# FPGA3.net
KiCad netlist of a schematic drawn in Altium Designer
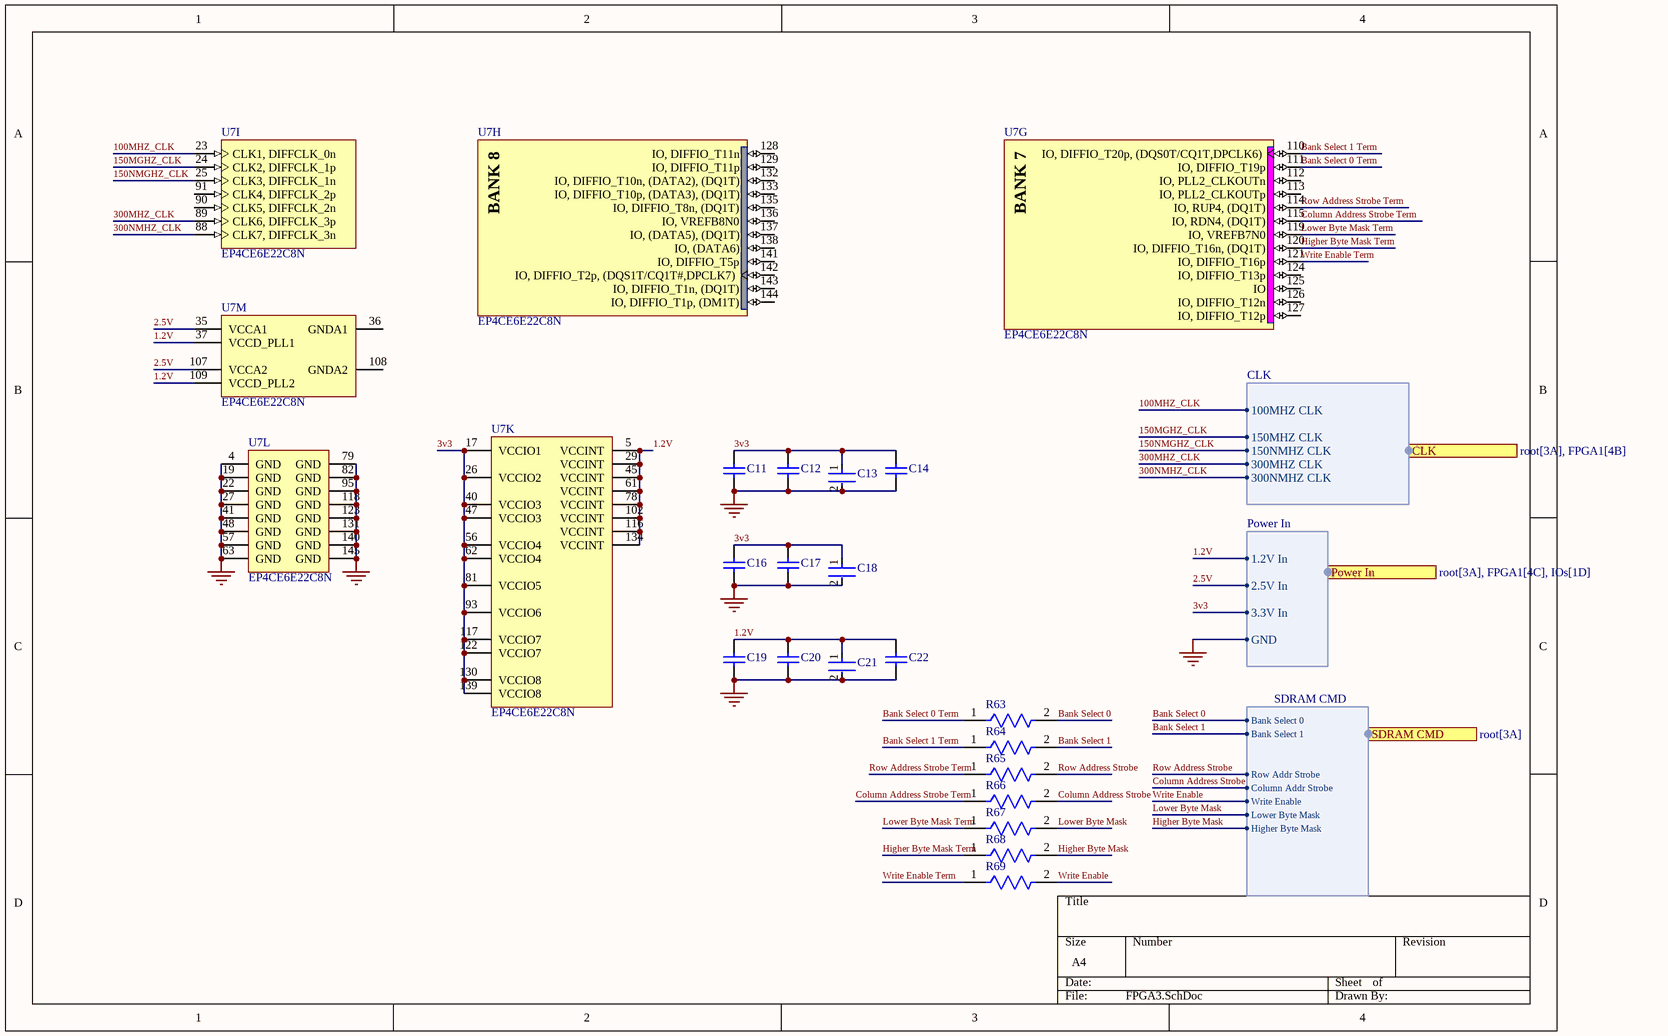
[diagram p0: FPGA3.SchDoc]

(export (version "E")
  (design (tool "Eeschema 10.0.6"))
  (components
    (comp (ref "C11")
      (value "C0603C105K9PACTU")
      (footprint "CAPC1608X90X35LL15T15")
      (fields (field (name "MANUFACTURER") "Kemet"))
      (libsource (lib "Altium Content Vault") (part "CAP"))
    )
    (comp (ref "C12")
      (value "C0603C105K9PACTU")
      (footprint "CAPC1608X90X35LL15T15")
      (fields (field (name "MANUFACTURER") "Kemet"))
      (libsource (lib "Altium Content Vault") (part "CAP"))
    )
    (comp (ref "C13")
      (value "GCG188R91H104MA01D")
      (footprint "FP-GCG188-0_2-IPC_B")
      (libsource (lib "Altium Content Vault") (part "02cd4be3c70576c341d710602a673aa"))
    )
    (comp (ref "C14")
      (value "C0805S472K5RACTU")
      (footprint "CAPC2013X145X50ML20T25")
      (fields (field (name "MANUFACTURER") "Kemet"))
      (libsource (lib "Altium Content Vault") (part "CAP"))
    )
    (comp (ref "C16")
      (value "C0603S102K4RACTU")
      (footprint "CAPC1608X87X35ML15T15")
      (fields (field (name "MANUFACTURER") "Kemet"))
      (libsource (lib "Altium Content Vault") (part "CAP"))
    )
    (comp (ref "C17")
      (value "C0805S472K5RACTU")
      (footprint "CAPC2013X145X50ML20T25")
      (fields (field (name "MANUFACTURER") "Kemet"))
      (libsource (lib "Altium Content Vault") (part "CAP"))
    )
    (comp (ref "C18")
      (value "GCG188R91H104MA01D")
      (footprint "FP-GCG188-0_2-IPC_B")
      (libsource (lib "Altium Content Vault") (part "02cd4be3c70576c341d710602a673aa"))
    )
    (comp (ref "C19")
      (value "C0603C105K9PACTU")
      (footprint "CAPC1608X90X35LL15T15")
      (fields (field (name "MANUFACTURER") "Kemet"))
      (libsource (lib "Altium Content Vault") (part "CAP"))
    )
    (comp (ref "C20")
      (value "C0603C105K9PACTU")
      (footprint "CAPC1608X90X35LL15T15")
      (fields (field (name "MANUFACTURER") "Kemet"))
      (libsource (lib "Altium Content Vault") (part "CAP"))
    )
    (comp (ref "C21")
      (value "GCG188R91H104MA01D")
      (footprint "FP-GCG188-0_2-IPC_B")
      (libsource (lib "Altium Content Vault") (part "02cd4be3c70576c341d710602a673aa"))
    )
    (comp (ref "C22")
      (value "C0805S472K5RACTU")
      (footprint "CAPC2013X145X50ML20T25")
      (fields (field (name "MANUFACTURER") "Kemet"))
      (libsource (lib "Altium Content Vault") (part "CAP"))
    )
    (comp (ref "R63")
      (value "RT0402BRE0750RL")
      (footprint "FP-RT0402-0_35-MFG")
      (fields (field (name "TOLERANCE") "0.1%"))
      (libsource (lib "Altium Content Vault") (part "1029c3af85768c4190bb7ad29bc67b5"))
    )
    (comp (ref "R64")
      (value "RT0402BRE0750RL")
      (footprint "FP-RT0402-0_35-MFG")
      (fields (field (name "TOLERANCE") "0.1%"))
      (libsource (lib "Altium Content Vault") (part "1029c3af85768c4190bb7ad29bc67b5"))
    )
    (comp (ref "R65")
      (value "RT0402BRE0750RL")
      (footprint "FP-RT0402-0_35-MFG")
      (fields (field (name "TOLERANCE") "0.1%"))
      (libsource (lib "Altium Content Vault") (part "1029c3af85768c4190bb7ad29bc67b5"))
    )
    (comp (ref "R66")
      (value "RT0402BRE0750RL")
      (footprint "FP-RT0402-0_35-MFG")
      (fields (field (name "TOLERANCE") "0.1%"))
      (libsource (lib "Altium Content Vault") (part "1029c3af85768c4190bb7ad29bc67b5"))
    )
    (comp (ref "R67")
      (value "RT0402BRE0750RL")
      (footprint "FP-RT0402-0_35-MFG")
      (fields (field (name "TOLERANCE") "0.1%"))
      (libsource (lib "Altium Content Vault") (part "1029c3af85768c4190bb7ad29bc67b5"))
    )
    (comp (ref "R68")
      (value "RT0402BRE0750RL")
      (footprint "FP-RT0402-0_35-MFG")
      (fields (field (name "TOLERANCE") "0.1%"))
      (libsource (lib "Altium Content Vault") (part "1029c3af85768c4190bb7ad29bc67b5"))
    )
    (comp (ref "R69")
      (value "RT0402BRE0750RL")
      (footprint "FP-RT0402-0_35-MFG")
      (fields (field (name "TOLERANCE") "0.1%"))
      (libsource (lib "Altium Content Vault") (part "1029c3af85768c4190bb7ad29bc67b5"))
    )
    (comp (ref "U7")
      (value "EP4CE6E22C8N")
      (footprint "EQFP144_A-165_D2-54_M")
      (fields (field (name "MANUFACTURER") "Altera"))
      (libsource (lib "Altium Content Vault") (part "FPGA-ALEP4C-EP4CE6-E144"))
    )
  )
  (nets
    (net (code "6") (name "/1.2V") (class "Default")
      (node (ref "C19") (pin "2") (pinfunction "2_2") (pintype "passive"))
      (node (ref "C20") (pin "2") (pinfunction "2_2") (pintype "passive"))
      (node (ref "C21") (pin "1") (pinfunction "1_1") (pintype "passive"))
      (node (ref "C22") (pin "2") (pinfunction "2_2") (pintype "passive"))
      (node (ref "U7") (pin "102") (pinfunction "VCCINT_102") (pintype "power_in"))
      (node (ref "U7") (pin "109") (pinfunction "VCCD_PLL2_109") (pintype "power_in"))
      (node (ref "U7") (pin "116") (pinfunction "VCCINT_116") (pintype "power_in"))
      (node (ref "U7") (pin "134") (pinfunction "VCCINT_134") (pintype "power_in"))
      (node (ref "U7") (pin "29") (pinfunction "VCCINT_29") (pintype "power_in"))
      (node (ref "U7") (pin "37") (pinfunction "VCCD_PLL1_37") (pintype "power_in"))
      (node (ref "U7") (pin "45") (pinfunction "VCCINT_45") (pintype "power_in"))
      (node (ref "U7") (pin "5") (pinfunction "VCCINT_5") (pintype "power_in"))
      (node (ref "U7") (pin "61") (pinfunction "VCCINT_61") (pintype "power_in"))
      (node (ref "U7") (pin "78") (pinfunction "VCCINT_78") (pintype "power_in"))
    )
    (net (code "7") (name "/2.5V") (class "Default")
      (node (ref "U7") (pin "107") (pinfunction "VCCA2_107") (pintype "power_in"))
      (node (ref "U7") (pin "35") (pinfunction "VCCA1_35") (pintype "power_in"))
    )
    (net (code "8") (name "/3v3") (class "Default")
      (node (ref "C11") (pin "2") (pinfunction "2_2") (pintype "passive"))
      (node (ref "C12") (pin "2") (pinfunction "2_2") (pintype "passive"))
      (node (ref "C13") (pin "1") (pinfunction "1_1") (pintype "passive"))
      (node (ref "C14") (pin "2") (pinfunction "2_2") (pintype "passive"))
      (node (ref "C16") (pin "2") (pinfunction "2_2") (pintype "passive"))
      (node (ref "C17") (pin "2") (pinfunction "2_2") (pintype "passive"))
      (node (ref "C18") (pin "1") (pinfunction "1_1") (pintype "passive"))
      (node (ref "U7") (pin "117") (pinfunction "VCCIO7_117") (pintype "power_in"))
      (node (ref "U7") (pin "122") (pinfunction "VCCIO7_122") (pintype "power_in"))
      (node (ref "U7") (pin "130") (pinfunction "VCCIO8_130") (pintype "power_in"))
      (node (ref "U7") (pin "139") (pinfunction "VCCIO8_139") (pintype "power_in"))
      (node (ref "U7") (pin "17") (pinfunction "VCCIO1_17") (pintype "power_in"))
      (node (ref "U7") (pin "26") (pinfunction "VCCIO2_26") (pintype "power_in"))
      (node (ref "U7") (pin "40") (pinfunction "VCCIO3_40") (pintype "power_in"))
      (node (ref "U7") (pin "47") (pinfunction "VCCIO3_47") (pintype "power_in"))
      (node (ref "U7") (pin "56") (pinfunction "VCCIO4_56") (pintype "power_in"))
      (node (ref "U7") (pin "62") (pinfunction "VCCIO4_62") (pintype "power_in"))
      (node (ref "U7") (pin "81") (pinfunction "VCCIO5_81") (pintype "power_in"))
      (node (ref "U7") (pin "93") (pinfunction "VCCIO6_93") (pintype "power_in"))
    )
    (net (code "9") (name "/100MHZ_CLK") (class "Default")
      (node (ref "U7") (pin "23") (pinfunction "CLK1,_DIFFCLK_0n_23") (pintype "input"))
    )
    (net (code "10") (name "/150MGHZ_CLK") (class "Default")
      (node (ref "U7") (pin "24") (pinfunction "CLK2,_DIFFCLK_1p_24") (pintype "input"))
    )
    (net (code "11") (name "/150NMGHZ_CLK") (class "Default")
      (node (ref "U7") (pin "25") (pinfunction "CLK3,_DIFFCLK_1n_25") (pintype "input"))
    )
    (net (code "12") (name "/300MHZ_CLK") (class "Default")
      (node (ref "U7") (pin "89") (pinfunction "CLK6,_DIFFCLK_3p_89") (pintype "input"))
    )
    (net (code "13") (name "/300NMHZ_CLK") (class "Default")
      (node (ref "U7") (pin "88") (pinfunction "CLK7,_DIFFCLK_3n_88") (pintype "input"))
    )
    (net (code "14") (name "/Bank Select 0") (class "Default")
      (node (ref "R63") (pin "2") (pinfunction "2_2") (pintype "passive"))
    )
    (net (code "15") (name "/Bank Select 0 Term") (class "Default")
      (node (ref "R63") (pin "1") (pinfunction "1_1") (pintype "passive"))
      (node (ref "U7") (pin "111") (pinfunction "IO,_DIFFIO_T19p_111") (pintype "bidirectional"))
    )
    (net (code "16") (name "/Bank Select 1") (class "Default")
      (node (ref "R64") (pin "2") (pinfunction "2_2") (pintype "passive"))
    )
    (net (code "17") (name "/Bank Select 1 Term") (class "Default")
      (node (ref "R64") (pin "1") (pinfunction "1_1") (pintype "passive"))
      (node (ref "U7") (pin "110") (pinfunction "IO,_DIFFIO_T20p,_(DQS0T/CQ1T,DPCLK6)_110") (pintype "bidirectional"))
    )
    (net (code "18") (name "/Column Address Strobe") (class "Default")
      (node (ref "R66") (pin "2") (pinfunction "2_2") (pintype "passive"))
    )
    (net (code "19") (name "/Column Address Strobe Term") (class "Default")
      (node (ref "R66") (pin "1") (pinfunction "1_1") (pintype "passive"))
      (node (ref "U7") (pin "115") (pinfunction "IO,_RDN4,_(DQ1T)_115") (pintype "bidirectional"))
    )
    (net (code "20") (name "/Higher Byte Mask") (class "Default")
      (node (ref "R68") (pin "2") (pinfunction "2_2") (pintype "passive"))
    )
    (net (code "21") (name "/Higher Byte Mask Term") (class "Default")
      (node (ref "R68") (pin "1") (pinfunction "1_1") (pintype "passive"))
      (node (ref "U7") (pin "120") (pinfunction "IO,_DIFFIO_T16n,_(DQ1T)_120") (pintype "bidirectional"))
    )
    (net (code "22") (name "/Lower Byte Mask") (class "Default")
      (node (ref "R67") (pin "2") (pinfunction "2_2") (pintype "passive"))
    )
    (net (code "23") (name "/Lower Byte Mask Term") (class "Default")
      (node (ref "R67") (pin "1") (pinfunction "1_1") (pintype "passive"))
      (node (ref "U7") (pin "119") (pinfunction "IO,_VREFB7N0_119") (pintype "bidirectional"))
    )
    (net (code "24") (name "/Row Address Strobe") (class "Default")
      (node (ref "R65") (pin "2") (pinfunction "2_2") (pintype "passive"))
    )
    (net (code "25") (name "/Row Address Strobe Term") (class "Default")
      (node (ref "R65") (pin "1") (pinfunction "1_1") (pintype "passive"))
      (node (ref "U7") (pin "114") (pinfunction "IO,_RUP4,_(DQ1T)_114") (pintype "bidirectional"))
    )
    (net (code "26") (name "/Write Enable") (class "Default")
      (node (ref "R69") (pin "2") (pinfunction "2_2") (pintype "passive"))
    )
    (net (code "27") (name "/Write Enable Term") (class "Default")
      (node (ref "R69") (pin "1") (pinfunction "1_1") (pintype "passive"))
      (node (ref "U7") (pin "121") (pinfunction "IO,_DIFFIO_T16p_121") (pintype "bidirectional"))
    )
    (net (code "31") (name "GND") (class "Default")
      (node (ref "C11") (pin "1") (pinfunction "1_1") (pintype "passive"))
      (node (ref "C12") (pin "1") (pinfunction "1_1") (pintype "passive"))
      (node (ref "C13") (pin "2") (pinfunction "2_2") (pintype "passive"))
      (node (ref "C14") (pin "1") (pinfunction "1_1") (pintype "passive"))
      (node (ref "C16") (pin "1") (pinfunction "1_1") (pintype "passive"))
      (node (ref "C17") (pin "1") (pinfunction "1_1") (pintype "passive"))
      (node (ref "C18") (pin "2") (pinfunction "2_2") (pintype "passive"))
      (node (ref "C19") (pin "1") (pinfunction "1_1") (pintype "passive"))
      (node (ref "C20") (pin "1") (pinfunction "1_1") (pintype "passive"))
      (node (ref "C21") (pin "2") (pinfunction "2_2") (pintype "passive"))
      (node (ref "C22") (pin "1") (pinfunction "1_1") (pintype "passive"))
      (node (ref "U7") (pin "118") (pinfunction "GND_118") (pintype "power_in"))
      (node (ref "U7") (pin "123") (pinfunction "GND_123") (pintype "power_in"))
      (node (ref "U7") (pin "131") (pinfunction "GND_131") (pintype "power_in"))
      (node (ref "U7") (pin "140") (pinfunction "GND_140") (pintype "power_in"))
      (node (ref "U7") (pin "145") (pinfunction "GND_145") (pintype "power_in"))
      (node (ref "U7") (pin "19") (pinfunction "GND_19") (pintype "power_in"))
      (node (ref "U7") (pin "22") (pinfunction "GND_22") (pintype "power_in"))
      (node (ref "U7") (pin "27") (pinfunction "GND_27") (pintype "power_in"))
      (node (ref "U7") (pin "4") (pinfunction "GND_4") (pintype "power_in"))
      (node (ref "U7") (pin "41") (pinfunction "GND_41") (pintype "power_in"))
      (node (ref "U7") (pin "48") (pinfunction "GND_48") (pintype "power_in"))
      (node (ref "U7") (pin "57") (pinfunction "GND_57") (pintype "power_in"))
      (node (ref "U7") (pin "63") (pinfunction "GND_63") (pintype "power_in"))
      (node (ref "U7") (pin "79") (pinfunction "GND_79") (pintype "power_in"))
      (node (ref "U7") (pin "82") (pinfunction "GND_82") (pintype "power_in"))
      (node (ref "U7") (pin "95") (pinfunction "GND_95") (pintype "power_in"))
    )
    (net (code "32") (name "unconnected-(U7G-IO,_DIFFIO_T12n-Pad126)") (class "Default")
      (node (ref "U7") (pin "126") (pinfunction "IO,_DIFFIO_T12n_126") (pintype "bidirectional"))
    )
    (net (code "33") (name "unconnected-(U7G-IO,_DIFFIO_T12p-Pad127)") (class "Default")
      (node (ref "U7") (pin "127") (pinfunction "IO,_DIFFIO_T12p_127") (pintype "bidirectional"))
    )
    (net (code "34") (name "unconnected-(U7G-IO,_DIFFIO_T13p-Pad124)") (class "Default")
      (node (ref "U7") (pin "124") (pinfunction "IO,_DIFFIO_T13p_124") (pintype "bidirectional"))
    )
    (net (code "35") (name "unconnected-(U7G-IO,_PLL2_CLKOUTn-Pad112)") (class "Default")
      (node (ref "U7") (pin "112") (pinfunction "IO,_PLL2_CLKOUTn_112") (pintype "bidirectional"))
    )
    (net (code "36") (name "unconnected-(U7G-IO,_PLL2_CLKOUTp-Pad113)") (class "Default")
      (node (ref "U7") (pin "113") (pinfunction "IO,_PLL2_CLKOUTp_113") (pintype "bidirectional"))
    )
    (net (code "37") (name "unconnected-(U7G-IO-Pad125)") (class "Default")
      (node (ref "U7") (pin "125") (pinfunction "IO_125") (pintype "bidirectional"))
    )
    (net (code "38") (name "unconnected-(U7H-IO,_(DATA5),_(DQ1T)-Pad137)") (class "Default")
      (node (ref "U7") (pin "137") (pinfunction "IO,_(DATA5),_(DQ1T)_137") (pintype "bidirectional"))
    )
    (net (code "39") (name "unconnected-(U7H-IO,_(DATA6)-Pad138)") (class "Default")
      (node (ref "U7") (pin "138") (pinfunction "IO,_(DATA6)_138") (pintype "bidirectional"))
    )
    (net (code "40") (name "unconnected-(U7H-IO,_DIFFIO_T1n,_(DQ1T)-Pad143)") (class "Default")
      (node (ref "U7") (pin "143") (pinfunction "IO,_DIFFIO_T1n,_(DQ1T)_143") (pintype "bidirectional"))
    )
    (net (code "41") (name "unconnected-(U7H-IO,_DIFFIO_T1p,_(DM1T)-Pad144)") (class "Default")
      (node (ref "U7") (pin "144") (pinfunction "IO,_DIFFIO_T1p,_(DM1T)_144") (pintype "bidirectional"))
    )
    (net (code "42") (name "unconnected-(U7H-IO,_DIFFIO_T2p,_(DQS1T{slash}CQ1T#,DPCLK7)-Pad142)") (class "Default")
      (node (ref "U7") (pin "142") (pinfunction "IO,_DIFFIO_T2p,_(DQS1T/CQ1T#,DPCLK7)_142") (pintype "bidirectional"))
    )
    (net (code "43") (name "unconnected-(U7H-IO,_DIFFIO_T5p-Pad141)") (class "Default")
      (node (ref "U7") (pin "141") (pinfunction "IO,_DIFFIO_T5p_141") (pintype "bidirectional"))
    )
    (net (code "44") (name "unconnected-(U7H-IO,_DIFFIO_T8n,_(DQ1T)-Pad135)") (class "Default")
      (node (ref "U7") (pin "135") (pinfunction "IO,_DIFFIO_T8n,_(DQ1T)_135") (pintype "bidirectional"))
    )
    (net (code "45") (name "unconnected-(U7H-IO,_DIFFIO_T10n,_(DATA2),_(DQ1T)-Pad132)") (class "Default")
      (node (ref "U7") (pin "132") (pinfunction "IO,_DIFFIO_T10n,_(DATA2),_(DQ1T)_132") (pintype "bidirectional"))
    )
    (net (code "46") (name "unconnected-(U7H-IO,_DIFFIO_T10p,_(DATA3),_(DQ1T)-Pad133)") (class "Default")
      (node (ref "U7") (pin "133") (pinfunction "IO,_DIFFIO_T10p,_(DATA3),_(DQ1T)_133") (pintype "bidirectional"))
    )
    (net (code "47") (name "unconnected-(U7H-IO,_DIFFIO_T11n-Pad128)") (class "Default")
      (node (ref "U7") (pin "128") (pinfunction "IO,_DIFFIO_T11n_128") (pintype "bidirectional"))
    )
    (net (code "48") (name "unconnected-(U7H-IO,_DIFFIO_T11p-Pad129)") (class "Default")
      (node (ref "U7") (pin "129") (pinfunction "IO,_DIFFIO_T11p_129") (pintype "bidirectional"))
    )
    (net (code "49") (name "unconnected-(U7H-IO,_VREFB8N0-Pad136)") (class "Default")
      (node (ref "U7") (pin "136") (pinfunction "IO,_VREFB8N0_136") (pintype "bidirectional"))
    )
    (net (code "50") (name "unconnected-(U7I-CLK4,_DIFFCLK_2p-Pad91)") (class "Default")
      (node (ref "U7") (pin "91") (pinfunction "CLK4,_DIFFCLK_2p_91") (pintype "input"))
    )
    (net (code "51") (name "unconnected-(U7I-CLK5,_DIFFCLK_2n-Pad90)") (class "Default")
      (node (ref "U7") (pin "90") (pinfunction "CLK5,_DIFFCLK_2n_90") (pintype "input"))
    )
    (net (code "52") (name "unconnected-(U7M-GNDA1-Pad36)") (class "Default")
      (node (ref "U7") (pin "36") (pinfunction "GNDA1_36") (pintype "power_in"))
    )
    (net (code "53") (name "unconnected-(U7M-GNDA2-Pad108)") (class "Default")
      (node (ref "U7") (pin "108") (pinfunction "GNDA2_108") (pintype "power_in"))
    )
  )
)
